# CANOPi_Baseboard_CAN.net
KiCad netlist of a schematic drawn in Altium Designer
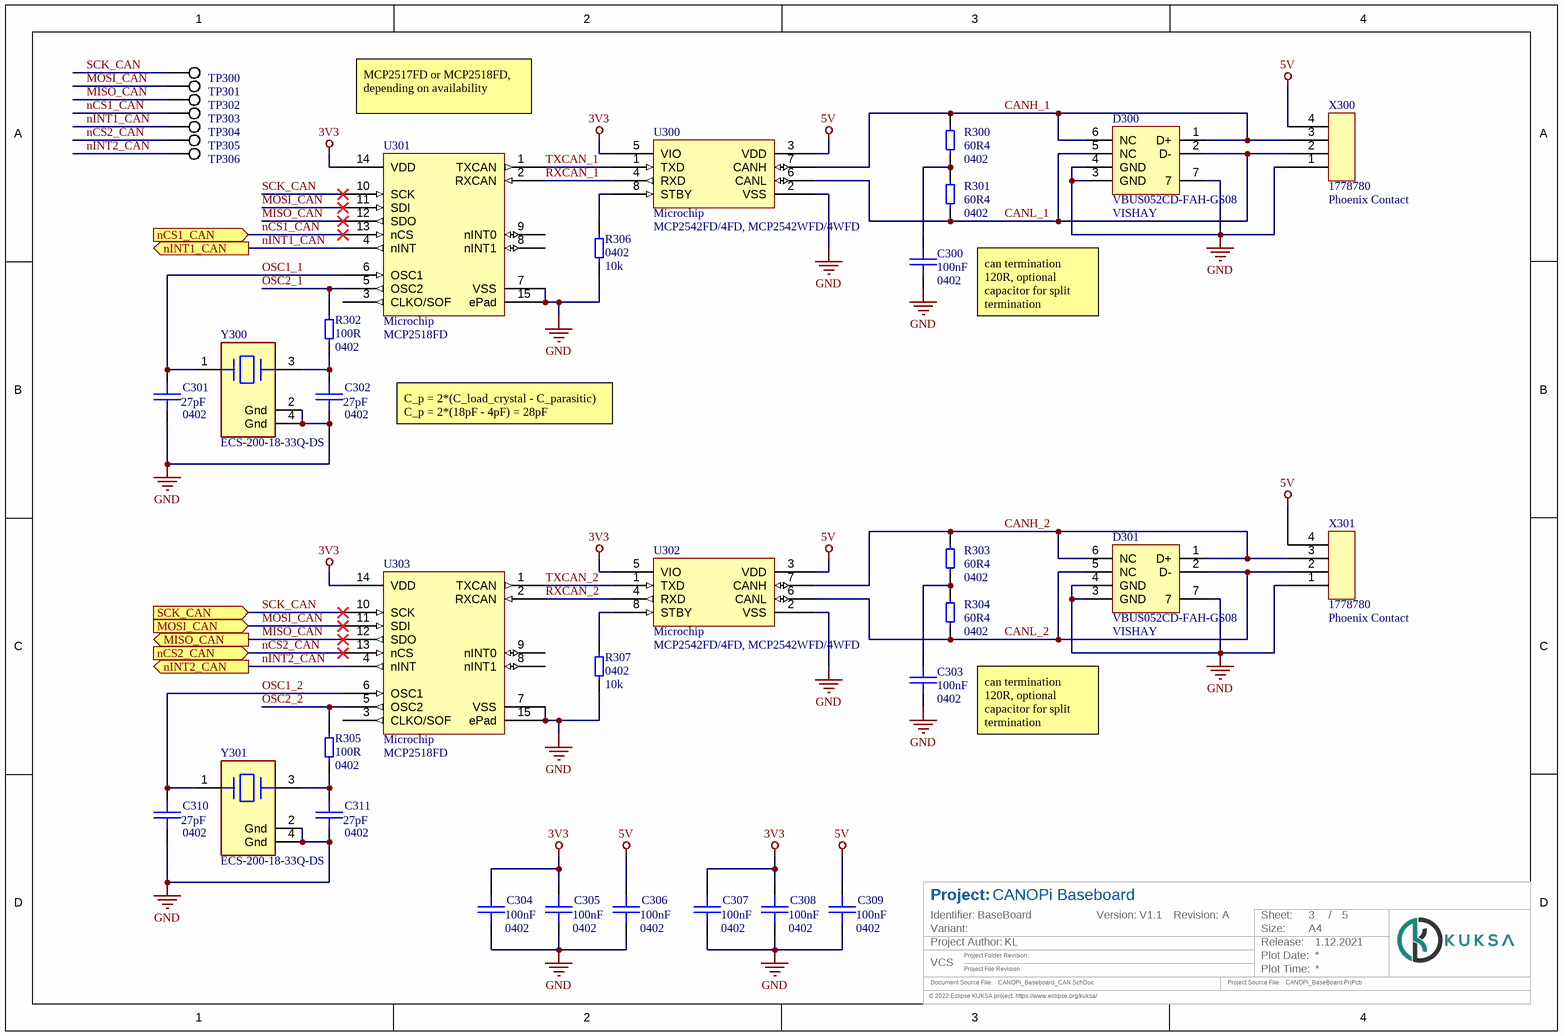
[diagram p0: CANOPi_Baseboard_CAN.SchDoc]

(export (version "E")
  (design (tool "Eeschema 10.0.6"))
  (components
    (comp (ref "C300")
      (value "CAP 0402 100n -10% +10% 6.3V X7R")
      (footprint "CAP 0402 [1005 Metric] X050 N")
      (description "SMD/SMT 0402 6.3V -10% +10% X7R - Multilayer Ceramic Capacitors MLCC")
      (fields
        (field (name "MANUFACTURER") "MURATA")
        (field (name "CAPACITANCE") "100nF")
        (field (name "MANUFACTURER PART NUMBER") "GRM155R70J104KA01#")
        (field (name "CASE") "0402")
      )
      (libsource (lib "ShareLib") (part "Capacitor non-polarized - Standard Schematic"))
    )
    (comp (ref "C301")
      (value "CAP 0402 27p -2% +2% 25V C0G")
      (footprint "CAP 0402 [1005 Metric] X050 N")
      (description "SMD/SMT 0402 25V -2% +2% C0G - Multilayer Ceramic Capacitors MLCC")
      (fields
        (field (name "MANUFACTURER") "MURATA")
        (field (name "CASE") "0402")
        (field (name "MANUFACTURER PART NUMBER") "GRM1555C1E270GA01#")
        (field (name "CAPACITANCE") "27pF")
      )
      (libsource (lib "ShareLib") (part "Capacitor non-polarized - Standard Schematic"))
    )
    (comp (ref "C302")
      (value "CAP 0402 27p -2% +2% 25V C0G")
      (footprint "CAP 0402 [1005 Metric] X050 N")
      (description "SMD/SMT 0402 25V -2% +2% C0G - Multilayer Ceramic Capacitors MLCC")
      (fields
        (field (name "MANUFACTURER") "MURATA")
        (field (name "CASE") "0402")
        (field (name "MANUFACTURER PART NUMBER") "GRM1555C1E270GA01#")
        (field (name "CAPACITANCE") "27pF")
      )
      (libsource (lib "ShareLib") (part "Capacitor non-polarized - Standard Schematic"))
    )
    (comp (ref "C303")
      (value "CAP 0402 100n -10% +10% 6.3V X7R")
      (footprint "CAP 0402 [1005 Metric] X050 N")
      (description "SMD/SMT 0402 6.3V -10% +10% X7R - Multilayer Ceramic Capacitors MLCC")
      (fields
        (field (name "MANUFACTURER") "MURATA")
        (field (name "CAPACITANCE") "100nF")
        (field (name "MANUFACTURER PART NUMBER") "GRM155R70J104KA01#")
        (field (name "CASE") "0402")
      )
      (libsource (lib "ShareLib") (part "Capacitor non-polarized - Standard Schematic"))
    )
    (comp (ref "C304")
      (value "CAP 0402 100n -10% +10% 6.3V X7R")
      (footprint "CAP 0402 [1005 Metric] X050 N")
      (description "SMD/SMT 0402 6.3V -10% +10% X7R - Multilayer Ceramic Capacitors MLCC")
      (fields
        (field (name "MANUFACTURER") "MURATA")
        (field (name "CAPACITANCE") "100nF")
        (field (name "MANUFACTURER PART NUMBER") "GRM155R70J104KA01#")
        (field (name "CASE") "0402")
      )
      (libsource (lib "ShareLib") (part "Capacitor non-polarized - Standard Schematic"))
    )
    (comp (ref "C305")
      (value "CAP 0402 100n -10% +10% 6.3V X7R")
      (footprint "CAP 0402 [1005 Metric] X050 N")
      (description "SMD/SMT 0402 6.3V -10% +10% X7R - Multilayer Ceramic Capacitors MLCC")
      (fields
        (field (name "MANUFACTURER") "MURATA")
        (field (name "CAPACITANCE") "100nF")
        (field (name "MANUFACTURER PART NUMBER") "GRM155R70J104KA01#")
        (field (name "CASE") "0402")
      )
      (libsource (lib "ShareLib") (part "Capacitor non-polarized - Standard Schematic"))
    )
    (comp (ref "C306")
      (value "CAP 0402 100n -10% +10% 6.3V X7R")
      (footprint "CAP 0402 [1005 Metric] X050 N")
      (description "SMD/SMT 0402 6.3V -10% +10% X7R - Multilayer Ceramic Capacitors MLCC")
      (fields
        (field (name "MANUFACTURER") "MURATA")
        (field (name "CAPACITANCE") "100nF")
        (field (name "MANUFACTURER PART NUMBER") "GRM155R70J104KA01#")
        (field (name "CASE") "0402")
      )
      (libsource (lib "ShareLib") (part "Capacitor non-polarized - Standard Schematic"))
    )
    (comp (ref "C307")
      (value "CAP 0402 100n -10% +10% 6.3V X7R")
      (footprint "CAP 0402 [1005 Metric] X050 N")
      (description "SMD/SMT 0402 6.3V -10% +10% X7R - Multilayer Ceramic Capacitors MLCC")
      (fields
        (field (name "MANUFACTURER") "MURATA")
        (field (name "CAPACITANCE") "100nF")
        (field (name "MANUFACTURER PART NUMBER") "GRM155R70J104KA01#")
        (field (name "CASE") "0402")
      )
      (libsource (lib "ShareLib") (part "Capacitor non-polarized - Standard Schematic"))
    )
    (comp (ref "C308")
      (value "CAP 0402 100n -10% +10% 6.3V X7R")
      (footprint "CAP 0402 [1005 Metric] X050 N")
      (description "SMD/SMT 0402 6.3V -10% +10% X7R - Multilayer Ceramic Capacitors MLCC")
      (fields
        (field (name "MANUFACTURER") "MURATA")
        (field (name "CAPACITANCE") "100nF")
        (field (name "MANUFACTURER PART NUMBER") "GRM155R70J104KA01#")
        (field (name "CASE") "0402")
      )
      (libsource (lib "ShareLib") (part "Capacitor non-polarized - Standard Schematic"))
    )
    (comp (ref "C309")
      (value "CAP 0402 100n -10% +10% 6.3V X7R")
      (footprint "CAP 0402 [1005 Metric] X050 N")
      (description "SMD/SMT 0402 6.3V -10% +10% X7R - Multilayer Ceramic Capacitors MLCC")
      (fields
        (field (name "MANUFACTURER") "MURATA")
        (field (name "CAPACITANCE") "100nF")
        (field (name "MANUFACTURER PART NUMBER") "GRM155R70J104KA01#")
        (field (name "CASE") "0402")
      )
      (libsource (lib "ShareLib") (part "Capacitor non-polarized - Standard Schematic"))
    )
    (comp (ref "C310")
      (value "CAP 0402 27p -2% +2% 25V C0G")
      (footprint "CAP 0402 [1005 Metric] X050 N")
      (description "SMD/SMT 0402 25V -2% +2% C0G - Multilayer Ceramic Capacitors MLCC")
      (fields
        (field (name "MANUFACTURER") "MURATA")
        (field (name "CASE") "0402")
        (field (name "MANUFACTURER PART NUMBER") "GRM1555C1E270GA01#")
        (field (name "CAPACITANCE") "27pF")
      )
      (libsource (lib "ShareLib") (part "Capacitor non-polarized - Standard Schematic"))
    )
    (comp (ref "C311")
      (value "CAP 0402 27p -2% +2% 25V C0G")
      (footprint "CAP 0402 [1005 Metric] X050 N")
      (description "SMD/SMT 0402 25V -2% +2% C0G - Multilayer Ceramic Capacitors MLCC")
      (fields
        (field (name "MANUFACTURER") "MURATA")
        (field (name "CASE") "0402")
        (field (name "MANUFACTURER PART NUMBER") "GRM1555C1E270GA01#")
        (field (name "CAPACITANCE") "27pF")
      )
      (libsource (lib "ShareLib") (part "Capacitor non-polarized - Standard Schematic"))
    )
    (comp (ref "D300")
      (value "VISHAY - VBUS052CD-FAH-GS08")
      (footprint "VISHAY - VBUS052CD-FAH")
      (description "2-Line BUS-Port ESD-Protection - Flow Through Design")
      (fields
        (field (name "MANUFACTURER PART NUMBER") "VBUS052CD-FAH-GS08")
        (field (name "MANUFACTURER") "VISHAY")
      )
      (libsource (lib "ShareLib") (part "VISHAY - VBUS052CD-FAH"))
    )
    (comp (ref "D301")
      (value "VISHAY - VBUS052CD-FAH-GS08")
      (footprint "VISHAY - VBUS052CD-FAH")
      (description "2-Line BUS-Port ESD-Protection - Flow Through Design")
      (fields
        (field (name "MANUFACTURER PART NUMBER") "VBUS052CD-FAH-GS08")
        (field (name "MANUFACTURER") "VISHAY")
      )
      (libsource (lib "ShareLib") (part "VISHAY - VBUS052CD-FAH"))
    )
    (comp (ref "R300")
      (value "RES 0402 60R4 1% 0W0625")
      (footprint "RES 0402 [1005 Metric]_N")
      (description "RC0402 series chip resistor with lead-free terminations made by thick film process")
      (fields
        (field (name "RESISTANCE") "60R4")
        (field (name "MANUFACTURER PART NUMBER") "RC0402FR-0760R4L")
        (field (name "MANUFACTURER") "YAGEO")
        (field (name "CASE") "0402")
      )
      (libsource (lib "ShareLib") (part "Standard Schematic - Resistor Universal"))
    )
    (comp (ref "R301")
      (value "RES 0402 60R4 1% 0W0625")
      (footprint "RES 0402 [1005 Metric]_N")
      (description "RC0402 series chip resistor with lead-free terminations made by thick film process")
      (fields
        (field (name "RESISTANCE") "60R4")
        (field (name "MANUFACTURER PART NUMBER") "RC0402FR-0760R4L")
        (field (name "MANUFACTURER") "YAGEO")
        (field (name "CASE") "0402")
      )
      (libsource (lib "ShareLib") (part "Standard Schematic - Resistor Universal"))
    )
    (comp (ref "R302")
      (value "RES 0402 100R 1% 63mW")
      (footprint "RES 0402 [1005 Metric]_N")
      (description "RC0402 series chip resistor with lead-free terminations made by thick film process")
      (fields
        (field (name "RESISTANCE") "100R")
        (field (name "CASE") "0402")
        (field (name "MANUFACTURER") "ROHM")
        (field (name "MANUFACTURER PART NUMBER") "MCR01MZPF100")
      )
      (libsource (lib "ShareLib") (part "Standard Schematic - Resistor Universal"))
    )
    (comp (ref "R303")
      (value "RES 0402 60R4 1% 0W0625")
      (footprint "RES 0402 [1005 Metric]_N")
      (description "RC0402 series chip resistor with lead-free terminations made by thick film process")
      (fields
        (field (name "RESISTANCE") "60R4")
        (field (name "MANUFACTURER PART NUMBER") "RC0402FR-0760R4L")
        (field (name "MANUFACTURER") "YAGEO")
        (field (name "CASE") "0402")
      )
      (libsource (lib "ShareLib") (part "Standard Schematic - Resistor Universal"))
    )
    (comp (ref "R304")
      (value "RES 0402 60R4 1% 0W0625")
      (footprint "RES 0402 [1005 Metric]_N")
      (description "RC0402 series chip resistor with lead-free terminations made by thick film process")
      (fields
        (field (name "RESISTANCE") "60R4")
        (field (name "MANUFACTURER PART NUMBER") "RC0402FR-0760R4L")
        (field (name "MANUFACTURER") "YAGEO")
        (field (name "CASE") "0402")
      )
      (libsource (lib "ShareLib") (part "Standard Schematic - Resistor Universal"))
    )
    (comp (ref "R305")
      (value "RES 0402 100R 1% 63mW")
      (footprint "RES 0402 [1005 Metric]_N")
      (description "RC0402 series chip resistor with lead-free terminations made by thick film process")
      (fields
        (field (name "RESISTANCE") "100R")
        (field (name "CASE") "0402")
        (field (name "MANUFACTURER") "ROHM")
        (field (name "MANUFACTURER PART NUMBER") "MCR01MZPF100")
      )
      (libsource (lib "ShareLib") (part "Standard Schematic - Resistor Universal"))
    )
    (comp (ref "R306")
      (value "RES 0402 10K 1% 0W0625")
      (footprint "RES 0402 [1005 Metric]_N")
      (description "RC0402 series chip resistor with lead-free terminations made by thick film process")
      (fields
        (field (name "MANUFACTURER PART NUMBER") "RC0402FR-0710KL")
        (field (name "CASE") "0402")
        (field (name "MANUFACTURER") "YAGEO")
        (field (name "RESISTANCE") "10k")
      )
      (libsource (lib "ShareLib") (part "Standard Schematic - Resistor Universal"))
    )
    (comp (ref "R307")
      (value "RES 0402 10K 1% 0W0625")
      (footprint "RES 0402 [1005 Metric]_N")
      (description "RC0402 series chip resistor with lead-free terminations made by thick film process")
      (fields
        (field (name "MANUFACTURER PART NUMBER") "RC0402FR-0710KL")
        (field (name "CASE") "0402")
        (field (name "MANUFACTURER") "YAGEO")
        (field (name "RESISTANCE") "10k")
      )
      (libsource (lib "ShareLib") (part "Standard Schematic - Resistor Universal"))
    )
    (comp (ref "TP300")
      (value "Testpad, 0.8mm x 0.8mm, round")
      (footprint "Testpad, 0.8mm x 0.8mm, round")
      (libsource (lib "ShareLib") (part "Testpoint (No BOM)"))
    )
    (comp (ref "TP301")
      (value "Testpad, 0.8mm x 0.8mm, round")
      (footprint "Testpad, 0.8mm x 0.8mm, round")
      (libsource (lib "ShareLib") (part "Testpoint (No BOM)"))
    )
    (comp (ref "TP302")
      (value "Testpad, 0.8mm x 0.8mm, round")
      (footprint "Testpad, 0.8mm x 0.8mm, round")
      (libsource (lib "ShareLib") (part "Testpoint (No BOM)"))
    )
    (comp (ref "TP303")
      (value "Testpad, 0.8mm x 0.8mm, round")
      (footprint "Testpad, 0.8mm x 0.8mm, round")
      (libsource (lib "ShareLib") (part "Testpoint (No BOM)"))
    )
    (comp (ref "TP304")
      (value "Testpad, 0.8mm x 0.8mm, round")
      (footprint "Testpad, 0.8mm x 0.8mm, round")
      (libsource (lib "ShareLib") (part "Testpoint (No BOM)"))
    )
    (comp (ref "TP305")
      (value "Testpad, 0.8mm x 0.8mm, round")
      (footprint "Testpad, 0.8mm x 0.8mm, round")
      (libsource (lib "ShareLib") (part "Testpoint (No BOM)"))
    )
    (comp (ref "TP306")
      (value "Testpad, 0.8mm x 0.8mm, round")
      (footprint "Testpad, 0.8mm x 0.8mm, round")
      (libsource (lib "ShareLib") (part "Testpoint (No BOM)"))
    )
    (comp (ref "U300")
      (value "MICROCHIP - MCP2542FD/4FD")
      (footprint "SOIC127P600X175-8N")
      (description "CAN FD Transceiver with Wake-up Pattern (WUP) Option")
      (fields
        (field (name "MANUFACTURER") "Microchip")
        (field (name "MANUFACTURER PART NUMBER") "MCP2542FD/4FD, MCP2542WFD/4WFD")
      )
      (libsource (lib "ShareLib") (part "MICROCHIP - MCP2542FD_4FD"))
    )
    (comp (ref "U301")
      (value "MICROCHIP - MCP2518FD")
      (footprint "SON65P300X90_HS-15N")
      (description "CAN FD Controller with SPI Interface")
      (fields (field (name "MANUFACTURER") "Microchip") (field (name "MANUFACTURER PART NUMBER") "MCP2518FD"))
      (libsource (lib "ShareLib") (part "Microchip - MCP2518FD"))
    )
    (comp (ref "U302")
      (value "MICROCHIP - MCP2542FD/4FD")
      (footprint "SOIC127P600X175-8N")
      (description "CAN FD Transceiver with Wake-up Pattern (WUP) Option")
      (fields
        (field (name "MANUFACTURER") "Microchip")
        (field (name "MANUFACTURER PART NUMBER") "MCP2542FD/4FD, MCP2542WFD/4WFD")
      )
      (libsource (lib "ShareLib") (part "MICROCHIP - MCP2542FD_4FD"))
    )
    (comp (ref "U303")
      (value "MICROCHIP - MCP2518FD")
      (footprint "SON65P300X90_HS-15N")
      (description "CAN FD Controller with SPI Interface")
      (fields (field (name "MANUFACTURER") "Microchip") (field (name "MANUFACTURER PART NUMBER") "MCP2518FD"))
      (libsource (lib "ShareLib") (part "Microchip - MCP2518FD"))
    )
    (comp (ref "X300")
      (value "PHOENIX CONTACT - PTSM 0,5/ 4-HH-2,5-SMD R32")
      (footprint "PHOENIX CONTACT - PTSM 0,5_ 4-HH-2,5-SMD R32-Footprint-1")
      (description "Leiterplatten-Grundleiste - PTSM 0,5/ 4-HH-2,5-SMD R32")
      (fields
        (field (name "MANUFACTURER PART NUMBER") "1778780")
        (field (name "MANUFACTURER") "Phoenix Contact")
      )
      (libsource (lib "ShareLib") (part "PHOENIX CONTACT - PTSM 0,5_ 4-HH-2,5-SMD R32"))
    )
    (comp (ref "X301")
      (value "PHOENIX CONTACT - PTSM 0,5/ 4-HH-2,5-SMD R32")
      (footprint "PHOENIX CONTACT - PTSM 0,5_ 4-HH-2,5-SMD R32-Footprint-1")
      (description "Leiterplatten-Grundleiste - PTSM 0,5/ 4-HH-2,5-SMD R32")
      (fields
        (field (name "MANUFACTURER PART NUMBER") "1778780")
        (field (name "MANUFACTURER") "Phoenix Contact")
      )
      (libsource (lib "ShareLib") (part "PHOENIX CONTACT - PTSM 0,5_ 4-HH-2,5-SMD R32"))
    )
    (comp (ref "Y300")
      (value "ECS-200-18-33Q-DS")
      (footprint "FP-ECX-33Q-MFG")
      (description "CRYSTAL 20.0000MHZ 18PF SMD")
      (fields
        (field (name "OCTOPART") "https://octopart.com/ecs-200-18-33q-ds-ecs+international-29290571")
        (field (name "TOLERANCE") "30ppm")
      )
      (libsource (lib "Altium Content Vault") (part "2e3fdc1e60336f3f4c57fc5a79d902f"))
    )
    (comp (ref "Y301")
      (value "ECS-200-18-33Q-DS")
      (footprint "FP-ECX-33Q-MFG")
      (description "CRYSTAL 20.0000MHZ 18PF SMD")
      (fields
        (field (name "OCTOPART") "https://octopart.com/ecs-200-18-33q-ds-ecs+international-29290571")
        (field (name "TOLERANCE") "30ppm")
      )
      (libsource (lib "Altium Content Vault") (part "2e3fdc1e60336f3f4c57fc5a79d902f"))
    )
  )
  (nets
    (net (code "1") (name "/CANH_1") (class "Default")
      (node (ref "D300") (pin "1") (pinfunction "D+_1") (pintype "passive"))
      (node (ref "D300") (pin "6") (pinfunction "NC_6") (pintype "passive"))
      (node (ref "R300") (pin "2") (pinfunction "2_2") (pintype "passive"))
      (node (ref "U300") (pin "7") (pinfunction "CANH_7") (pintype "bidirectional"))
      (node (ref "X300") (pin "3") (pintype "passive"))
    )
    (net (code "2") (name "/CANH_2") (class "Default")
      (node (ref "D301") (pin "1") (pinfunction "D+_1") (pintype "passive"))
      (node (ref "D301") (pin "6") (pinfunction "NC_6") (pintype "passive"))
      (node (ref "R303") (pin "2") (pinfunction "2_2") (pintype "passive"))
      (node (ref "U302") (pin "7") (pinfunction "CANH_7") (pintype "bidirectional"))
      (node (ref "X301") (pin "3") (pintype "passive"))
    )
    (net (code "3") (name "/CANL_1") (class "Default")
      (node (ref "D300") (pin "2") (pinfunction "D-_2") (pintype "passive"))
      (node (ref "D300") (pin "5") (pinfunction "NC_5") (pintype "passive"))
      (node (ref "R301") (pin "1") (pinfunction "1_1") (pintype "passive"))
      (node (ref "U300") (pin "6") (pinfunction "CANL_6") (pintype "bidirectional"))
      (node (ref "X300") (pin "2") (pintype "passive"))
    )
    (net (code "4") (name "/CANL_2") (class "Default")
      (node (ref "D301") (pin "2") (pinfunction "D-_2") (pintype "passive"))
      (node (ref "D301") (pin "5") (pinfunction "NC_5") (pintype "passive"))
      (node (ref "R304") (pin "1") (pinfunction "1_1") (pintype "passive"))
      (node (ref "U302") (pin "6") (pinfunction "CANL_6") (pintype "bidirectional"))
      (node (ref "X301") (pin "2") (pintype "passive"))
    )
    (net (code "5") (name "/MISO_CAN") (class "Default")
      (node (ref "TP302") (pin "1") (pinfunction "1_1") (pintype "passive"))
      (node (ref "U301") (pin "12") (pinfunction "SDO_12") (pintype "output"))
      (node (ref "U303") (pin "12") (pinfunction "SDO_12") (pintype "output"))
    )
    (net (code "6") (name "/MOSI_CAN") (class "Default")
      (node (ref "TP301") (pin "1") (pinfunction "1_1") (pintype "passive"))
      (node (ref "U301") (pin "11") (pinfunction "SDI_11") (pintype "input"))
      (node (ref "U303") (pin "11") (pinfunction "SDI_11") (pintype "input"))
    )
    (net (code "7") (name "/OSC1_1") (class "Default")
      (node (ref "C301") (pin "2") (pinfunction "2_2") (pintype "passive"))
      (node (ref "U301") (pin "6") (pinfunction "OSC1_6") (pintype "input"))
      (node (ref "Y300") (pin "1") (pinfunction "In/Out_1") (pintype "passive"))
    )
    (net (code "8") (name "/OSC1_2") (class "Default")
      (node (ref "C310") (pin "2") (pinfunction "2_2") (pintype "passive"))
      (node (ref "U303") (pin "6") (pinfunction "OSC1_6") (pintype "input"))
      (node (ref "Y301") (pin "1") (pinfunction "In/Out_1") (pintype "passive"))
    )
    (net (code "9") (name "/OSC2_1") (class "Default")
      (node (ref "R302") (pin "2") (pinfunction "2_2") (pintype "passive"))
      (node (ref "U301") (pin "5") (pinfunction "OSC2_5") (pintype "output"))
    )
    (net (code "10") (name "/OSC2_2") (class "Default")
      (node (ref "R305") (pin "2") (pinfunction "2_2") (pintype "passive"))
      (node (ref "U303") (pin "5") (pinfunction "OSC2_5") (pintype "output"))
    )
    (net (code "11") (name "/RXCAN_1") (class "Default")
      (node (ref "U300") (pin "4") (pinfunction "RXD_4") (pintype "output"))
      (node (ref "U301") (pin "2") (pinfunction "RXCAN_2") (pintype "input"))
    )
    (net (code "12") (name "/RXCAN_2") (class "Default")
      (node (ref "U302") (pin "4") (pinfunction "RXD_4") (pintype "output"))
      (node (ref "U303") (pin "2") (pinfunction "RXCAN_2") (pintype "input"))
    )
    (net (code "13") (name "/SCK_CAN") (class "Default")
      (node (ref "TP300") (pin "1") (pinfunction "1_1") (pintype "passive"))
      (node (ref "U301") (pin "10") (pinfunction "SCK_10") (pintype "input"))
      (node (ref "U303") (pin "10") (pinfunction "SCK_10") (pintype "input"))
    )
    (net (code "14") (name "/TXCAN_1") (class "Default")
      (node (ref "U300") (pin "1") (pinfunction "TXD_1") (pintype "input"))
      (node (ref "U301") (pin "1") (pinfunction "TXCAN_1") (pintype "output"))
    )
    (net (code "15") (name "/TXCAN_2") (class "Default")
      (node (ref "U302") (pin "1") (pinfunction "TXD_1") (pintype "input"))
      (node (ref "U303") (pin "1") (pinfunction "TXCAN_1") (pintype "output"))
    )
    (net (code "16") (name "/nCS1_CAN") (class "Default")
      (node (ref "TP303") (pin "1") (pinfunction "1_1") (pintype "passive"))
      (node (ref "U301") (pin "13") (pinfunction "nCS_13") (pintype "input"))
    )
    (net (code "17") (name "/nCS2_CAN") (class "Default")
      (node (ref "TP305") (pin "1") (pinfunction "1_1") (pintype "passive"))
      (node (ref "U303") (pin "13") (pinfunction "nCS_13") (pintype "input"))
    )
    (net (code "18") (name "/nINT1_CAN") (class "Default")
      (node (ref "TP304") (pin "1") (pinfunction "1_1") (pintype "passive"))
      (node (ref "U301") (pin "4") (pinfunction "nINT_4") (pintype "output"))
    )
    (net (code "19") (name "/nINT2_CAN") (class "Default")
      (node (ref "TP306") (pin "1") (pinfunction "1_1") (pintype "passive"))
      (node (ref "U303") (pin "4") (pinfunction "nINT_4") (pintype "output"))
    )
    (net (code "20") (name "3V3") (class "Default")
      (node (ref "C304") (pin "2") (pinfunction "2_2") (pintype "passive"))
      (node (ref "C305") (pin "2") (pinfunction "2_2") (pintype "passive"))
      (node (ref "C307") (pin "2") (pinfunction "2_2") (pintype "passive"))
      (node (ref "C308") (pin "2") (pinfunction "2_2") (pintype "passive"))
      (node (ref "U300") (pin "5") (pinfunction "VIO_5") (pintype "power_in"))
      (node (ref "U301") (pin "14") (pinfunction "VDD_14") (pintype "power_in"))
      (node (ref "U302") (pin "5") (pinfunction "VIO_5") (pintype "power_in"))
      (node (ref "U303") (pin "14") (pinfunction "VDD_14") (pintype "power_in"))
    )
    (net (code "21") (name "5V") (class "Default")
      (node (ref "C306") (pin "2") (pinfunction "2_2") (pintype "passive"))
      (node (ref "C309") (pin "2") (pinfunction "2_2") (pintype "passive"))
      (node (ref "U300") (pin "3") (pinfunction "VDD_3") (pintype "power_in"))
      (node (ref "U302") (pin "3") (pinfunction "VDD_3") (pintype "power_in"))
      (node (ref "X300") (pin "4") (pintype "passive"))
      (node (ref "X301") (pin "4") (pintype "passive"))
    )
    (net (code "22") (name "GND") (class "Default")
      (node (ref "C300") (pin "2") (pinfunction "2_2") (pintype "passive"))
      (node (ref "C301") (pin "1") (pinfunction "1_1") (pintype "passive"))
      (node (ref "C302") (pin "1") (pinfunction "1_1") (pintype "passive"))
      (node (ref "C303") (pin "2") (pinfunction "2_2") (pintype "passive"))
      (node (ref "C304") (pin "1") (pinfunction "1_1") (pintype "passive"))
      (node (ref "C305") (pin "1") (pinfunction "1_1") (pintype "passive"))
      (node (ref "C306") (pin "1") (pinfunction "1_1") (pintype "passive"))
      (node (ref "C307") (pin "1") (pinfunction "1_1") (pintype "passive"))
      (node (ref "C308") (pin "1") (pinfunction "1_1") (pintype "passive"))
      (node (ref "C309") (pin "1") (pinfunction "1_1") (pintype "passive"))
      (node (ref "C310") (pin "1") (pinfunction "1_1") (pintype "passive"))
      (node (ref "C311") (pin "1") (pinfunction "1_1") (pintype "passive"))
      (node (ref "D300") (pin "3") (pinfunction "GND_3") (pintype "power_in"))
      (node (ref "D300") (pin "4") (pinfunction "GND_4") (pintype "power_in"))
      (node (ref "D300") (pin "7") (pinfunction "7_7") (pintype "passive"))
      (node (ref "D301") (pin "3") (pinfunction "GND_3") (pintype "power_in"))
      (node (ref "D301") (pin "4") (pinfunction "GND_4") (pintype "power_in"))
      (node (ref "D301") (pin "7") (pinfunction "7_7") (pintype "passive"))
      (node (ref "R306") (pin "2") (pinfunction "2_2") (pintype "passive"))
      (node (ref "R307") (pin "2") (pinfunction "2_2") (pintype "passive"))
      (node (ref "U300") (pin "2") (pinfunction "VSS_2") (pintype "power_in"))
      (node (ref "U301") (pin "15") (pinfunction "ePad_15") (pintype "power_in"))
      (node (ref "U301") (pin "7") (pinfunction "VSS_7") (pintype "power_in"))
      (node (ref "U302") (pin "2") (pinfunction "VSS_2") (pintype "power_in"))
      (node (ref "U303") (pin "15") (pinfunction "ePad_15") (pintype "power_in"))
      (node (ref "U303") (pin "7") (pinfunction "VSS_7") (pintype "power_in"))
      (node (ref "X300") (pin "1") (pintype "passive"))
      (node (ref "X301") (pin "1") (pintype "passive"))
      (node (ref "Y300") (pin "2") (pinfunction "Gnd_2") (pintype "power_in"))
      (node (ref "Y300") (pin "4") (pinfunction "Gnd_4") (pintype "power_in"))
      (node (ref "Y301") (pin "2") (pinfunction "Gnd_2") (pintype "power_in"))
      (node (ref "Y301") (pin "4") (pinfunction "Gnd_4") (pintype "power_in"))
    )
    (net (code "23") (name "Net-(C300-Pad1)") (class "Default")
      (node (ref "C300") (pin "1") (pinfunction "1_1") (pintype "passive"))
      (node (ref "R300") (pin "1") (pinfunction "1_1") (pintype "passive"))
      (node (ref "R301") (pin "2") (pinfunction "2_2") (pintype "passive"))
    )
    (net (code "24") (name "Net-(C303-Pad1)") (class "Default")
      (node (ref "C303") (pin "1") (pinfunction "1_1") (pintype "passive"))
      (node (ref "R303") (pin "1") (pinfunction "1_1") (pintype "passive"))
      (node (ref "R304") (pin "2") (pinfunction "2_2") (pintype "passive"))
    )
    (net (code "25") (name "Net-(U300-STBY)") (class "Default")
      (node (ref "R306") (pin "1") (pinfunction "1_1") (pintype "passive"))
      (node (ref "U300") (pin "8") (pinfunction "STBY_8") (pintype "input"))
    )
    (net (code "26") (name "Net-(U302-STBY)") (class "Default")
      (node (ref "R307") (pin "1") (pinfunction "1_1") (pintype "passive"))
      (node (ref "U302") (pin "8") (pinfunction "STBY_8") (pintype "input"))
    )
    (net (code "27") (name "Net-(Y300-Out{slash}In)") (class "Default")
      (node (ref "C302") (pin "2") (pinfunction "2_2") (pintype "passive"))
      (node (ref "R302") (pin "1") (pinfunction "1_1") (pintype "passive"))
      (node (ref "Y300") (pin "3") (pinfunction "Out/In_3") (pintype "passive"))
    )
    (net (code "28") (name "Net-(Y301-Out{slash}In)") (class "Default")
      (node (ref "C311") (pin "2") (pinfunction "2_2") (pintype "passive"))
      (node (ref "R305") (pin "1") (pinfunction "1_1") (pintype "passive"))
      (node (ref "Y301") (pin "3") (pinfunction "Out/In_3") (pintype "passive"))
    )
    (net (code "29") (name "unconnected-(U301-CLKO{slash}SOF-Pad3)") (class "Default")
      (node (ref "U301") (pin "3") (pinfunction "CLKO/SOF_3") (pintype "output"))
    )
    (net (code "30") (name "unconnected-(U301-nINT0-Pad9)") (class "Default")
      (node (ref "U301") (pin "9") (pinfunction "nINT0_9") (pintype "bidirectional"))
    )
    (net (code "31") (name "unconnected-(U301-nINT1-Pad8)") (class "Default")
      (node (ref "U301") (pin "8") (pinfunction "nINT1_8") (pintype "bidirectional"))
    )
    (net (code "32") (name "unconnected-(U303-CLKO{slash}SOF-Pad3)") (class "Default")
      (node (ref "U303") (pin "3") (pinfunction "CLKO/SOF_3") (pintype "output"))
    )
    (net (code "33") (name "unconnected-(U303-nINT0-Pad9)") (class "Default")
      (node (ref "U303") (pin "9") (pinfunction "nINT0_9") (pintype "bidirectional"))
    )
    (net (code "34") (name "unconnected-(U303-nINT1-Pad8)") (class "Default")
      (node (ref "U303") (pin "8") (pinfunction "nINT1_8") (pintype "bidirectional"))
    )
  )
)
